# POWER_SUPPLIES.net
KiCad netlist of a schematic drawn in Altium Designer
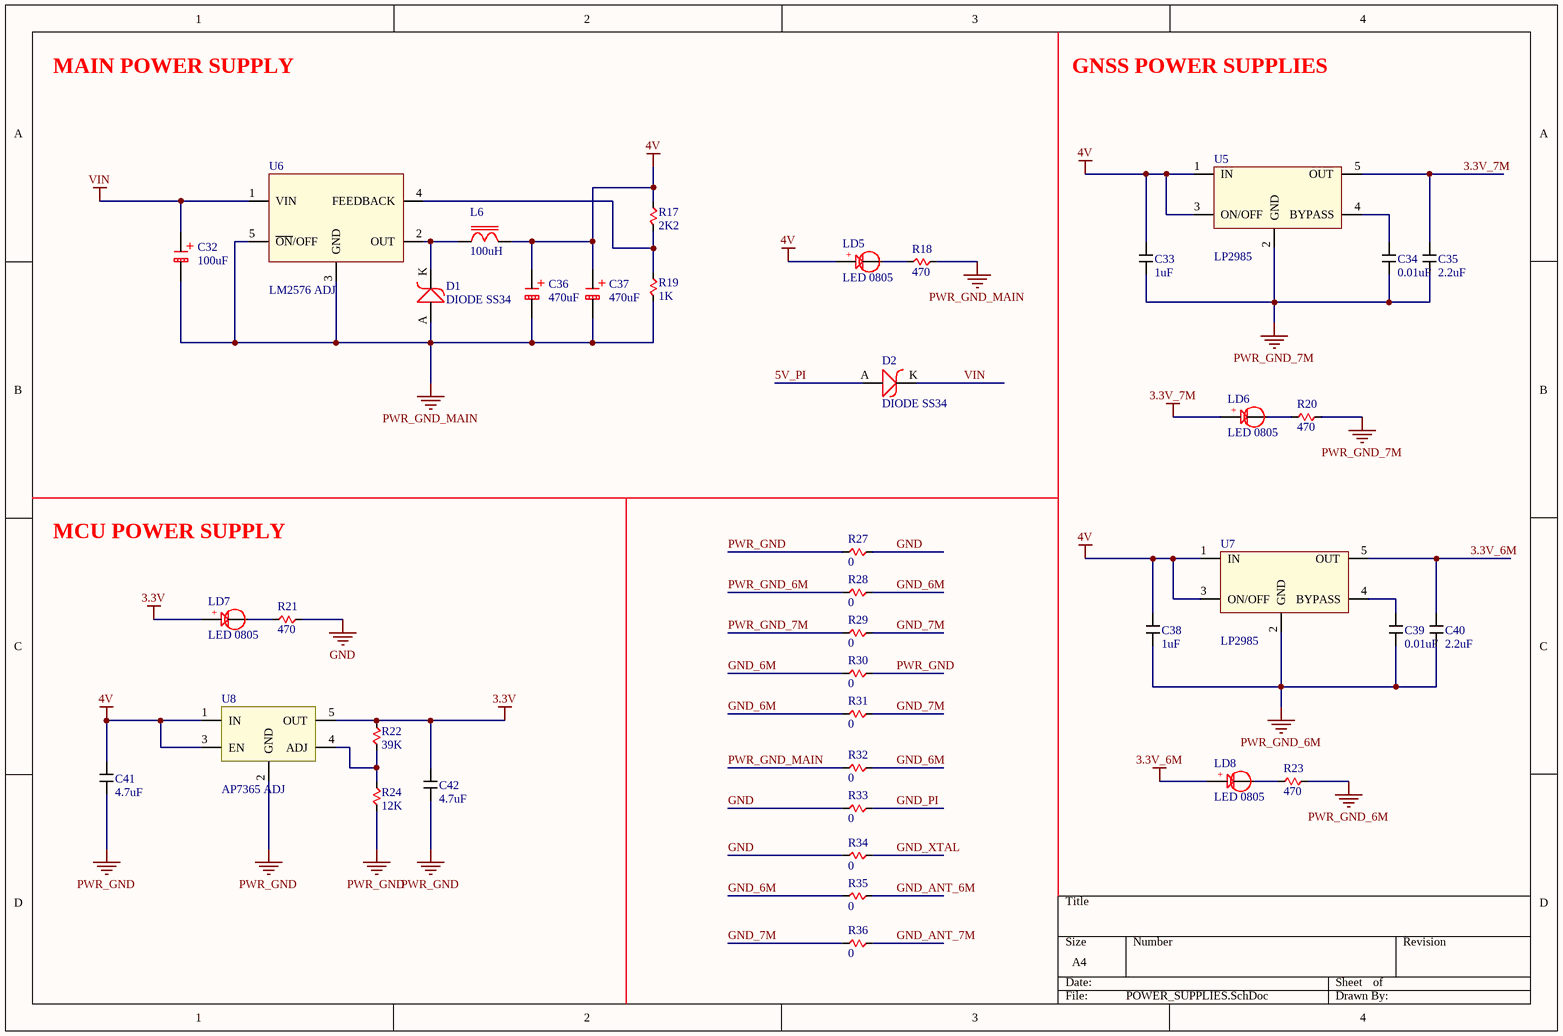
[diagram p0: POWER_SUPPLIES.SchDoc]

(export (version "E")
  (design (tool "Eeschema 10.0.6"))
  (components
    (comp (ref "C32")
      (value "100uF")
      (footprint "C TATAL 3528")
      (description "C TATAL 3528")
      (libsource (lib "SkyWar") (part "C TATAL 3528"))
    )
    (comp (ref "C33") (value "1uF") (footprint "C 0805") (libsource (lib "SkyWar") (part "C 0805")))
    (comp (ref "C34") (value "0.01uF") (footprint "C 0805") (libsource (lib "SkyWar") (part "C 0805")))
    (comp (ref "C35") (value "2.2uF") (footprint "C 0805") (libsource (lib "SkyWar") (part "C 0805")))
    (comp (ref "C36")
      (value "470uF")
      (footprint "C TATAL 7343")
      (description "C TATAL 7343")
      (libsource (lib "SkyWar") (part "C TATAL 7343"))
    )
    (comp (ref "C37")
      (value "470uF")
      (footprint "C TATAL 7343")
      (description "C TATAL 7343")
      (libsource (lib "SkyWar") (part "C TATAL 7343"))
    )
    (comp (ref "C38") (value "1uF") (footprint "C 0805") (libsource (lib "SkyWar") (part "C 0805")))
    (comp (ref "C39") (value "0.01uF") (footprint "C 0805") (libsource (lib "SkyWar") (part "C 0805")))
    (comp (ref "C40") (value "2.2uF") (footprint "C 0805") (libsource (lib "SkyWar") (part "C 0805")))
    (comp (ref "C41") (value "4.7uF") (footprint "C 0805") (libsource (lib "SkyWar") (part "C 0805")))
    (comp (ref "C42") (value "4.7uF") (footprint "C 0805") (libsource (lib "SkyWar") (part "C 0805")))
    (comp (ref "D1")
      (value "DIODE SS34")
      (footprint "DIODE SS34")
      (libsource (lib "SkyWar") (part "DIODE SS34"))
    )
    (comp (ref "D2")
      (value "DIODE SS34")
      (footprint "DIODE SS34")
      (libsource (lib "SkyWar") (part "DIODE SS34"))
    )
    (comp (ref "L6") (value "100uH") (footprint "L 4600") (libsource (lib "SkyWar") (part "L 4600")))
    (comp (ref "LD5") (value "LED 0805") (footprint "LED 0805") (libsource (lib "SkyWar") (part "LED 0805")))
    (comp (ref "LD6") (value "LED 0805") (footprint "LED 0805") (libsource (lib "SkyWar") (part "LED 0805")))
    (comp (ref "LD7") (value "LED 0805") (footprint "LED 0805") (libsource (lib "SkyWar") (part "LED 0805")))
    (comp (ref "LD8") (value "LED 0805") (footprint "LED 0805") (libsource (lib "SkyWar") (part "LED 0805")))
    (comp (ref "R17") (value "2K2") (footprint "R 0805") (libsource (lib "SkyWar") (part "R 0805")))
    (comp (ref "R18") (value "470") (footprint "R 0805") (libsource (lib "SkyWar") (part "R 0805")))
    (comp (ref "R19") (value "1K") (footprint "R 0805") (libsource (lib "SkyWar") (part "R 0805")))
    (comp (ref "R20") (value "470") (footprint "R 0805") (libsource (lib "SkyWar") (part "R 0805")))
    (comp (ref "R21") (value "470") (footprint "R 0805") (libsource (lib "SkyWar") (part "R 0805")))
    (comp (ref "R22") (value "39K") (footprint "R 0805") (libsource (lib "SkyWar") (part "R 0805")))
    (comp (ref "R23") (value "470") (footprint "R 0805") (libsource (lib "SkyWar") (part "R 0805")))
    (comp (ref "R24") (value "12K") (footprint "R 0805") (libsource (lib "SkyWar") (part "R 0805")))
    (comp (ref "R27") (value "0") (footprint "R 0805") (libsource (lib "SkyWar") (part "R 0805")))
    (comp (ref "R28") (value "0") (footprint "R 0805") (libsource (lib "SkyWar") (part "R 0805")))
    (comp (ref "R29") (value "0") (footprint "R 0805") (libsource (lib "SkyWar") (part "R 0805")))
    (comp (ref "R30") (value "0") (footprint "R 0805") (libsource (lib "SkyWar") (part "R 0805")))
    (comp (ref "R31") (value "0") (footprint "R 0805") (libsource (lib "SkyWar") (part "R 0805")))
    (comp (ref "R32") (value "0") (footprint "R 0805") (libsource (lib "SkyWar") (part "R 0805")))
    (comp (ref "R33") (value "0") (footprint "R 0805") (libsource (lib "SkyWar") (part "R 0805")))
    (comp (ref "R34") (value "0") (footprint "R 0805") (libsource (lib "SkyWar") (part "R 0805")))
    (comp (ref "R35") (value "0") (footprint "R 0805") (libsource (lib "SkyWar") (part "R 0805")))
    (comp (ref "R36") (value "0") (footprint "R 0805") (libsource (lib "SkyWar") (part "R 0805")))
    (comp (ref "U5") (value "LP2985") (footprint "LP2985") (libsource (lib "SkyWar") (part "LP2985 LDO")))
    (comp (ref "U6")
      (value "LM2576 ADJ")
      (footprint "LM2576 ADJ")
      (libsource (lib "SkyWar") (part "LM2576 ADJ"))
    )
    (comp (ref "U7") (value "LP2985") (footprint "LP2985") (libsource (lib "SkyWar") (part "LP2985 LDO")))
    (comp (ref "U8")
      (value "AP7365 ADJ")
      (footprint "AP7365 ADJ")
      (libsource (lib "SkyWar") (part "AP7365 ADJ"))
    )
  )
  (nets
    (net (code "1") (name "/5V_PI") (class "Default") (node (ref "D2") (pin "A") (pintype "passive")))
    (net (code "2") (name "/GND_6M") (class "Default")
      (node (ref "R28") (pin "2") (pinfunction "1_2") (pintype "passive"))
      (node (ref "R30") (pin "1") (pinfunction "0_1") (pintype "passive"))
      (node (ref "R31") (pin "1") (pinfunction "0_1") (pintype "passive"))
      (node (ref "R32") (pin "2") (pinfunction "1_2") (pintype "passive"))
      (node (ref "R35") (pin "1") (pinfunction "0_1") (pintype "passive"))
    )
    (net (code "3") (name "/GND_7M") (class "Default")
      (node (ref "R29") (pin "2") (pinfunction "1_2") (pintype "passive"))
      (node (ref "R31") (pin "2") (pinfunction "1_2") (pintype "passive"))
      (node (ref "R36") (pin "1") (pinfunction "0_1") (pintype "passive"))
    )
    (net (code "4") (name "/GND_ANT_6M") (class "Default")
      (node (ref "R35") (pin "2") (pinfunction "1_2") (pintype "passive"))
    )
    (net (code "5") (name "/GND_ANT_7M") (class "Default")
      (node (ref "R36") (pin "2") (pinfunction "1_2") (pintype "passive"))
    )
    (net (code "6") (name "/GND_PI") (class "Default")
      (node (ref "R33") (pin "2") (pinfunction "1_2") (pintype "passive"))
    )
    (net (code "7") (name "/GND_XTAL") (class "Default")
      (node (ref "R34") (pin "2") (pinfunction "1_2") (pintype "passive"))
    )
    (net (code "8") (name "3.3V") (class "Default")
      (node (ref "C42") (pin "1") (pintype "passive"))
      (node (ref "LD7") (pin "1") (pinfunction "3_1") (pintype "passive"))
      (node (ref "R22") (pin "1") (pinfunction "0_1") (pintype "passive"))
      (node (ref "U8") (pin "5") (pinfunction "OUT_5") (pintype "passive"))
    )
    (net (code "9") (name "3.3V_6M") (class "Default")
      (node (ref "C40") (pin "2") (pintype "passive"))
      (node (ref "LD8") (pin "1") (pinfunction "3_1") (pintype "passive"))
      (node (ref "U7") (pin "5") (pinfunction "OUT_5") (pintype "passive"))
    )
    (net (code "10") (name "3.3V_7M") (class "Default")
      (node (ref "C35") (pin "2") (pintype "passive"))
      (node (ref "LD6") (pin "1") (pinfunction "3_1") (pintype "passive"))
      (node (ref "U5") (pin "5") (pinfunction "OUT_5") (pintype "passive"))
    )
    (net (code "11") (name "4V") (class "Default")
      (node (ref "C33") (pin "2") (pintype "passive"))
      (node (ref "C36") (pin "1") (pintype "passive"))
      (node (ref "C37") (pin "1") (pintype "passive"))
      (node (ref "C38") (pin "2") (pintype "passive"))
      (node (ref "C41") (pin "1") (pintype "passive"))
      (node (ref "L6") (pin "2") (pintype "passive"))
      (node (ref "LD5") (pin "1") (pinfunction "3_1") (pintype "passive"))
      (node (ref "R17") (pin "2") (pinfunction "1_2") (pintype "passive"))
      (node (ref "U5") (pin "1") (pinfunction "IN_1") (pintype "passive"))
      (node (ref "U5") (pin "3") (pinfunction "ON/OFF_3") (pintype "passive"))
      (node (ref "U7") (pin "1") (pinfunction "IN_1") (pintype "passive"))
      (node (ref "U7") (pin "3") (pinfunction "ON/OFF_3") (pintype "passive"))
      (node (ref "U8") (pin "1") (pinfunction "IN_1") (pintype "passive"))
      (node (ref "U8") (pin "3") (pinfunction "EN_3") (pintype "passive"))
    )
    (net (code "12") (name "GND") (class "Default")
      (node (ref "R21") (pin "1") (pinfunction "0_1") (pintype "passive"))
      (node (ref "R27") (pin "2") (pinfunction "1_2") (pintype "passive"))
      (node (ref "R33") (pin "1") (pinfunction "0_1") (pintype "passive"))
      (node (ref "R34") (pin "1") (pinfunction "0_1") (pintype "passive"))
    )
    (net (code "13") (name "Net-(LD5-4)") (class "Default")
      (node (ref "LD5") (pin "2") (pinfunction "4_2") (pintype "passive"))
      (node (ref "R18") (pin "2") (pinfunction "1_2") (pintype "passive"))
    )
    (net (code "14") (name "Net-(LD6-4)") (class "Default")
      (node (ref "LD6") (pin "2") (pinfunction "4_2") (pintype "passive"))
      (node (ref "R20") (pin "2") (pinfunction "1_2") (pintype "passive"))
    )
    (net (code "15") (name "Net-(LD7-4)") (class "Default")
      (node (ref "LD7") (pin "2") (pinfunction "4_2") (pintype "passive"))
      (node (ref "R21") (pin "2") (pinfunction "1_2") (pintype "passive"))
    )
    (net (code "16") (name "Net-(LD8-4)") (class "Default")
      (node (ref "LD8") (pin "2") (pinfunction "4_2") (pintype "passive"))
      (node (ref "R23") (pin "2") (pinfunction "1_2") (pintype "passive"))
    )
    (net (code "17") (name "Net-(R17-0)") (class "Default")
      (node (ref "R17") (pin "1") (pinfunction "0_1") (pintype "passive"))
      (node (ref "R19") (pin "2") (pinfunction "1_2") (pintype "passive"))
      (node (ref "U6") (pin "4") (pinfunction "FEEDBACK_4") (pintype "passive"))
    )
    (net (code "18") (name "Net-(R22-1)") (class "Default")
      (node (ref "R22") (pin "2") (pinfunction "1_2") (pintype "passive"))
      (node (ref "R24") (pin "1") (pinfunction "0_1") (pintype "passive"))
      (node (ref "U8") (pin "4") (pinfunction "ADJ_4") (pintype "passive"))
    )
    (net (code "19") (name "Net-(U5-BYPASS)") (class "Default")
      (node (ref "C34") (pin "2") (pintype "passive"))
      (node (ref "U5") (pin "4") (pinfunction "BYPASS_4") (pintype "passive"))
    )
    (net (code "20") (name "Net-(U6-OUT)") (class "Default")
      (node (ref "D1") (pin "K") (pintype "passive"))
      (node (ref "L6") (pin "1") (pintype "passive"))
      (node (ref "U6") (pin "2") (pinfunction "OUT_2") (pintype "passive"))
    )
    (net (code "21") (name "Net-(U7-BYPASS)") (class "Default")
      (node (ref "C39") (pin "2") (pintype "passive"))
      (node (ref "U7") (pin "4") (pinfunction "BYPASS_4") (pintype "passive"))
    )
    (net (code "22") (name "PWR_GND") (class "Default")
      (node (ref "C41") (pin "2") (pintype "passive"))
      (node (ref "C42") (pin "2") (pintype "passive"))
      (node (ref "R24") (pin "2") (pinfunction "1_2") (pintype "passive"))
      (node (ref "R27") (pin "1") (pinfunction "0_1") (pintype "passive"))
      (node (ref "R30") (pin "2") (pinfunction "1_2") (pintype "passive"))
      (node (ref "U8") (pin "2") (pinfunction "GND_2") (pintype "passive"))
    )
    (net (code "23") (name "PWR_GND_6M") (class "Default")
      (node (ref "C38") (pin "1") (pintype "passive"))
      (node (ref "C39") (pin "1") (pintype "passive"))
      (node (ref "C40") (pin "1") (pintype "passive"))
      (node (ref "R23") (pin "1") (pinfunction "0_1") (pintype "passive"))
      (node (ref "R28") (pin "1") (pinfunction "0_1") (pintype "passive"))
      (node (ref "U7") (pin "2") (pinfunction "GND_2") (pintype "passive"))
    )
    (net (code "24") (name "PWR_GND_7M") (class "Default")
      (node (ref "C33") (pin "1") (pintype "passive"))
      (node (ref "C34") (pin "1") (pintype "passive"))
      (node (ref "C35") (pin "1") (pintype "passive"))
      (node (ref "R20") (pin "1") (pinfunction "0_1") (pintype "passive"))
      (node (ref "R29") (pin "1") (pinfunction "0_1") (pintype "passive"))
      (node (ref "U5") (pin "2") (pinfunction "GND_2") (pintype "passive"))
    )
    (net (code "25") (name "PWR_GND_MAIN") (class "Default")
      (node (ref "C32") (pin "2") (pintype "passive"))
      (node (ref "C36") (pin "2") (pintype "passive"))
      (node (ref "C37") (pin "2") (pintype "passive"))
      (node (ref "D1") (pin "A") (pintype "passive"))
      (node (ref "R18") (pin "1") (pinfunction "0_1") (pintype "passive"))
      (node (ref "R19") (pin "1") (pinfunction "0_1") (pintype "passive"))
      (node (ref "R32") (pin "1") (pinfunction "0_1") (pintype "passive"))
      (node (ref "U6") (pin "3") (pinfunction "GND_3") (pintype "passive"))
      (node (ref "U6") (pin "5") (pinfunction "~{ON}/OFF_5") (pintype "passive"))
    )
    (net (code "26") (name "VIN") (class "Default")
      (node (ref "C32") (pin "1") (pintype "passive"))
      (node (ref "D2") (pin "K") (pintype "passive"))
      (node (ref "U6") (pin "1") (pinfunction "VIN_1") (pintype "passive"))
    )
  )
)
